# Analog_Channel_Test.net
KiCad netlist of a schematic drawn in Altium Designer
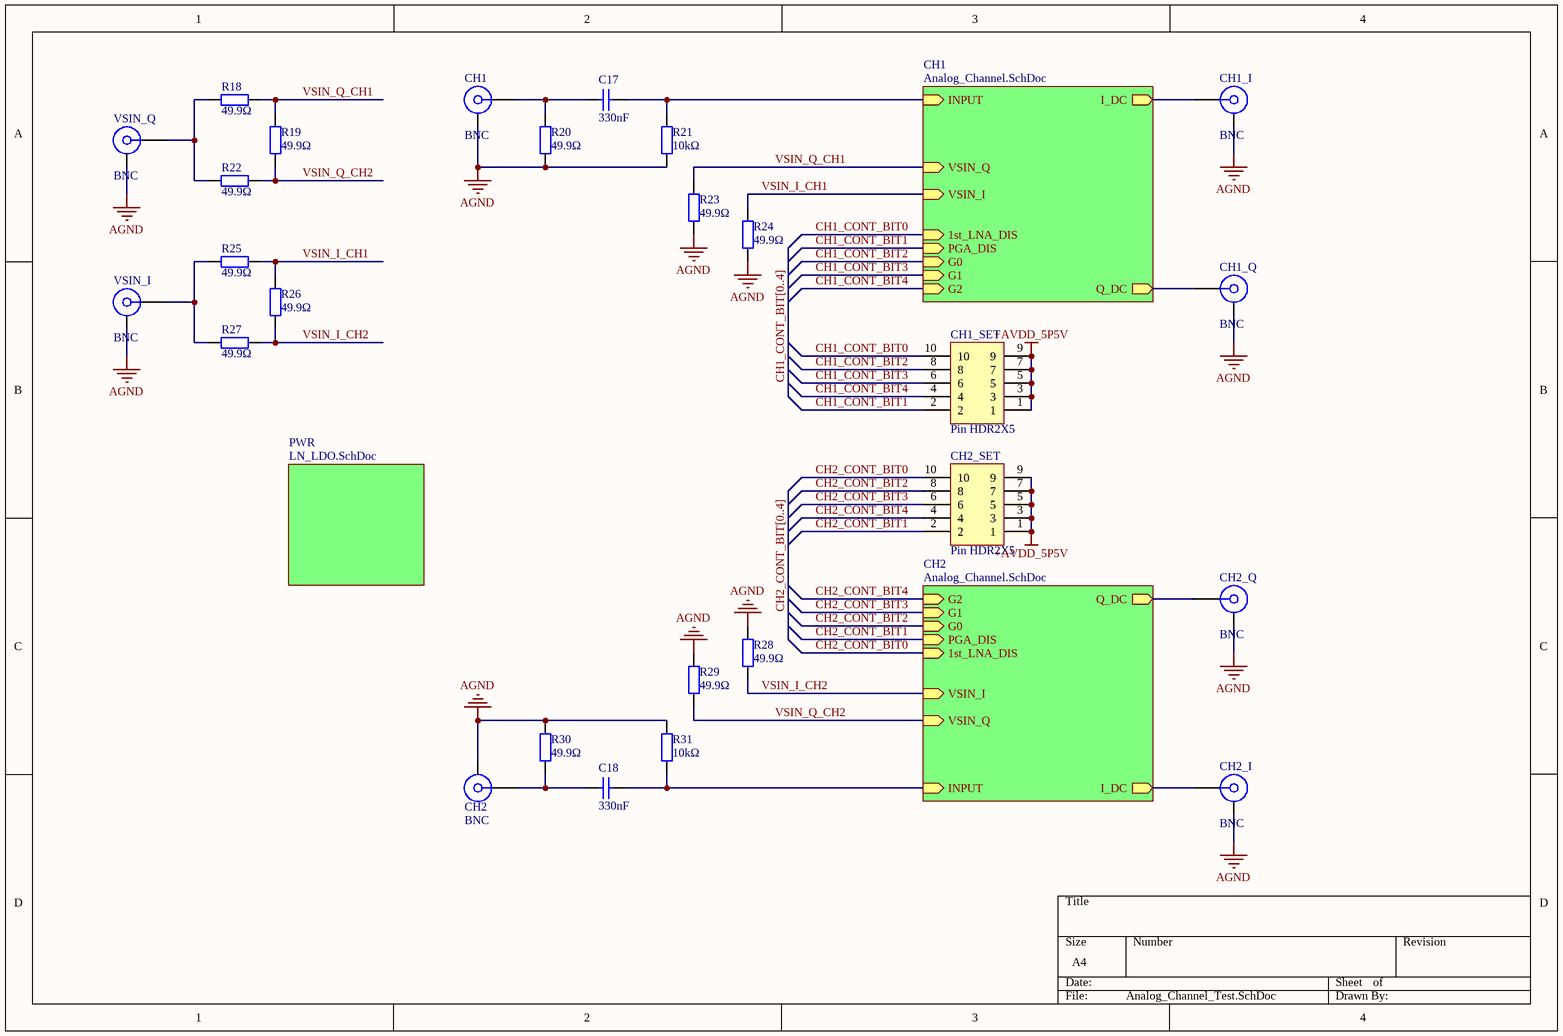
[diagram p0: Analog_Channel_Test.SchDoc]

(export (version "E")
  (design (tool "Eeschema 10.0.6"))
  (components
    (comp (ref "C17")
      (value "330nF")
      (footprint "1206_C")
      (description "贴片电容")
      (libsource (lib "Miscellaneous Devices LC") (part "1206 100nF (104) 10% 50V"))
    )
    (comp (ref "C18")
      (value "330nF")
      (footprint "1206_C")
      (description "贴片电容")
      (libsource (lib "Miscellaneous Devices LC") (part "1206 100nF (104) 10% 50V"))
    )
    (comp (ref "CH1")
      (value "BNC")
      (footprint "BNC-TYCO_1-1337542-0")
      (description "BNC-KE PIN 6.9mm distance")
      (fields (field (name "PARTNUMBER") "51K101-400A4"))
      (libsource (lib "OlvkLib") (part "BNC"))
    )
    (comp (ref "CH1_I")
      (value "BNC")
      (footprint "BNC-TYCO_1-1337542-0")
      (description "BNC-KE PIN 6.9mm distance")
      (fields (field (name "PARTNUMBER") "51K101-400A4"))
      (libsource (lib "OlvkLib") (part "BNC"))
    )
    (comp (ref "CH1_Q")
      (value "BNC")
      (footprint "BNC-TYCO_1-1337542-0")
      (description "BNC-KE PIN 6.9mm distance")
      (fields (field (name "PARTNUMBER") "51K101-400A4"))
      (libsource (lib "OlvkLib") (part "BNC"))
    )
    (comp (ref "CH1_SET")
      (value "Pin HDR2X5")
      (footprint "Pin HDR2X5/2.54mm-S")
      (libsource (lib "排针") (part "Pin HDR2X5"))
    )
    (comp (ref "CH2")
      (value "BNC")
      (footprint "BNC-TYCO_1-1337542-0")
      (description "BNC-KE PIN 6.9mm distance")
      (fields (field (name "PARTNUMBER") "51K101-400A4"))
      (libsource (lib "OlvkLib") (part "BNC"))
    )
    (comp (ref "CH2_I")
      (value "BNC")
      (footprint "BNC-TYCO_1-1337542-0")
      (description "BNC-KE PIN 6.9mm distance")
      (fields (field (name "PARTNUMBER") "51K101-400A4"))
      (libsource (lib "OlvkLib") (part "BNC"))
    )
    (comp (ref "CH2_Q")
      (value "BNC")
      (footprint "BNC-TYCO_1-1337542-0")
      (description "BNC-KE PIN 6.9mm distance")
      (fields (field (name "PARTNUMBER") "51K101-400A4"))
      (libsource (lib "OlvkLib") (part "BNC"))
    )
    (comp (ref "CH2_SET")
      (value "Pin HDR2X5")
      (footprint "Pin HDR2X5/2.54mm-S")
      (libsource (lib "排针") (part "Pin HDR2X5"))
    )
    (comp (ref "R18")
      (value "49.9Ω")
      (footprint "0603_R")
      (description "贴片电阻")
      (libsource (lib "Miscellaneous Devices LC") (part "0603 49.9Ω (49R9) 1%"))
    )
    (comp (ref "R19")
      (value "49.9Ω")
      (footprint "0603_R")
      (description "贴片电阻")
      (libsource (lib "") (part "0603 49.9Ω (49R9) 1%_2"))
    )
    (comp (ref "R20")
      (value "49.9Ω")
      (footprint "0603_R")
      (description "贴片电阻")
      (libsource (lib "") (part "0603 49.9Ω (49R9) 1%_1"))
    )
    (comp (ref "R21")
      (value "10kΩ")
      (footprint "0603_R")
      (description "贴片电阻")
      (libsource (lib "Miscellaneous Devices LC") (part "0603 10KΩ (1002) 1%"))
    )
    (comp (ref "R22")
      (value "49.9Ω")
      (footprint "0603_R")
      (description "贴片电阻")
      (libsource (lib "Miscellaneous Devices LC") (part "0603 49.9Ω (49R9) 1%"))
    )
    (comp (ref "R23")
      (value "49.9Ω")
      (footprint "0603_R")
      (description "贴片电阻")
      (libsource (lib "") (part "0603 49.9Ω (49R9) 1%_1"))
    )
    (comp (ref "R24")
      (value "49.9Ω")
      (footprint "0603_R")
      (description "贴片电阻")
      (libsource (lib "") (part "0603 49.9Ω (49R9) 1%_1"))
    )
    (comp (ref "R25")
      (value "49.9Ω")
      (footprint "0603_R")
      (description "贴片电阻")
      (libsource (lib "Miscellaneous Devices LC") (part "0603 49.9Ω (49R9) 1%"))
    )
    (comp (ref "R26")
      (value "49.9Ω")
      (footprint "0603_R")
      (description "贴片电阻")
      (libsource (lib "") (part "0603 49.9Ω (49R9) 1%_2"))
    )
    (comp (ref "R27")
      (value "49.9Ω")
      (footprint "0603_R")
      (description "贴片电阻")
      (libsource (lib "Miscellaneous Devices LC") (part "0603 49.9Ω (49R9) 1%"))
    )
    (comp (ref "R28")
      (value "49.9Ω")
      (footprint "0603_R")
      (description "贴片电阻")
      (libsource (lib "Miscellaneous Devices LC") (part "0603 49.9Ω (49R9) 1%"))
    )
    (comp (ref "R29")
      (value "49.9Ω")
      (footprint "0603_R")
      (description "贴片电阻")
      (libsource (lib "Miscellaneous Devices LC") (part "0603 49.9Ω (49R9) 1%"))
    )
    (comp (ref "R30")
      (value "49.9Ω")
      (footprint "0603_R")
      (description "贴片电阻")
      (libsource (lib "Miscellaneous Devices LC") (part "0603 49.9Ω (49R9) 1%"))
    )
    (comp (ref "R31")
      (value "10kΩ")
      (footprint "0603_R")
      (description "贴片电阻")
      (libsource (lib "") (part "0603 10KΩ (1002) 1%_1"))
    )
    (comp (ref "VSIN_I")
      (value "BNC")
      (footprint "BNC-TYCO_1-1337542-0")
      (description "BNC-KE PIN 6.9mm distance")
      (fields (field (name "PARTNUMBER") "51K101-400A4"))
      (libsource (lib "OlvkLib") (part "BNC"))
    )
    (comp (ref "VSIN_Q")
      (value "BNC")
      (footprint "BNC-TYCO_1-1337542-0")
      (description "BNC-KE PIN 6.9mm distance")
      (fields (field (name "PARTNUMBER") "51K101-400A4"))
      (libsource (lib "OlvkLib") (part "BNC"))
    )
  )
  (nets
    (net (code "1") (name "+AVDD_5P5V") (class "Default")
      (node (ref "CH1_SET") (pin "1") (pinfunction "1_1") (pintype "passive"))
      (node (ref "CH1_SET") (pin "3") (pinfunction "3_3") (pintype "passive"))
      (node (ref "CH1_SET") (pin "5") (pinfunction "5_5") (pintype "passive"))
      (node (ref "CH1_SET") (pin "7") (pinfunction "7_7") (pintype "passive"))
      (node (ref "CH1_SET") (pin "9") (pinfunction "9_9") (pintype "passive"))
      (node (ref "CH2_SET") (pin "1") (pinfunction "1_1") (pintype "passive"))
      (node (ref "CH2_SET") (pin "3") (pinfunction "3_3") (pintype "passive"))
      (node (ref "CH2_SET") (pin "5") (pinfunction "5_5") (pintype "passive"))
      (node (ref "CH2_SET") (pin "7") (pinfunction "7_7") (pintype "passive"))
      (node (ref "CH2_SET") (pin "9") (pinfunction "9_9") (pintype "passive"))
    )
    (net (code "2") (name "/CH1_CONT_BIT0") (class "Default")
      (node (ref "CH1_SET") (pin "10") (pinfunction "10_10") (pintype "passive"))
    )
    (net (code "3") (name "/CH1_CONT_BIT1") (class "Default")
      (node (ref "CH1_SET") (pin "2") (pinfunction "2_2") (pintype "passive"))
    )
    (net (code "4") (name "/CH1_CONT_BIT2") (class "Default")
      (node (ref "CH1_SET") (pin "8") (pinfunction "8_8") (pintype "passive"))
    )
    (net (code "5") (name "/CH1_CONT_BIT3") (class "Default")
      (node (ref "CH1_SET") (pin "6") (pinfunction "6_6") (pintype "passive"))
    )
    (net (code "6") (name "/CH1_CONT_BIT4") (class "Default")
      (node (ref "CH1_SET") (pin "4") (pinfunction "4_4") (pintype "passive"))
    )
    (net (code "8") (name "/CH2_CONT_BIT0") (class "Default")
      (node (ref "CH2_SET") (pin "10") (pinfunction "10_10") (pintype "passive"))
    )
    (net (code "9") (name "/CH2_CONT_BIT1") (class "Default")
      (node (ref "CH2_SET") (pin "2") (pinfunction "2_2") (pintype "passive"))
    )
    (net (code "10") (name "/CH2_CONT_BIT2") (class "Default")
      (node (ref "CH2_SET") (pin "8") (pinfunction "8_8") (pintype "passive"))
    )
    (net (code "11") (name "/CH2_CONT_BIT3") (class "Default")
      (node (ref "CH2_SET") (pin "6") (pinfunction "6_6") (pintype "passive"))
    )
    (net (code "12") (name "/CH2_CONT_BIT4") (class "Default")
      (node (ref "CH2_SET") (pin "4") (pinfunction "4_4") (pintype "passive"))
    )
    (net (code "14") (name "/INPUT") (class "Default")
      (node (ref "C17") (pin "2") (pinfunction "2_2") (pintype "passive"))
      (node (ref "R21") (pin "2") (pinfunction "2_2") (pintype "passive"))
    )
    (net (code "15") (name "/INPUT_1") (class "Default")
      (node (ref "C18") (pin "2") (pinfunction "2_2") (pintype "passive"))
      (node (ref "R31") (pin "2") (pinfunction "2_2") (pintype "passive"))
    )
    (net (code "16") (name "/I_DC") (class "Default")
      (node (ref "CH1_I") (pin "1") (pinfunction "1_1") (pintype "passive"))
    )
    (net (code "17") (name "/I_DC_1") (class "Default")
      (node (ref "CH2_I") (pin "1") (pinfunction "1_1") (pintype "passive"))
    )
    (net (code "18") (name "/Q_DC") (class "Default")
      (node (ref "CH1_Q") (pin "1") (pinfunction "1_1") (pintype "passive"))
    )
    (net (code "19") (name "/Q_DC_1") (class "Default")
      (node (ref "CH2_Q") (pin "1") (pinfunction "1_1") (pintype "passive"))
    )
    (net (code "20") (name "/VSIN_I_CH1") (class "Default")
      (node (ref "R24") (pin "2") (pinfunction "2_2") (pintype "passive"))
      (node (ref "R25") (pin "1") (pinfunction "1_1") (pintype "passive"))
      (node (ref "R26") (pin "1") (pinfunction "1_1") (pintype "passive"))
    )
    (net (code "21") (name "/VSIN_I_CH2") (class "Default")
      (node (ref "R26") (pin "2") (pinfunction "2_2") (pintype "passive"))
      (node (ref "R27") (pin "1") (pinfunction "1_1") (pintype "passive"))
      (node (ref "R28") (pin "2") (pinfunction "2_2") (pintype "passive"))
    )
    (net (code "22") (name "/VSIN_Q_CH1") (class "Default")
      (node (ref "R18") (pin "1") (pinfunction "1_1") (pintype "passive"))
      (node (ref "R19") (pin "1") (pinfunction "1_1") (pintype "passive"))
      (node (ref "R23") (pin "2") (pinfunction "2_2") (pintype "passive"))
    )
    (net (code "23") (name "/VSIN_Q_CH2") (class "Default")
      (node (ref "R19") (pin "2") (pinfunction "2_2") (pintype "passive"))
      (node (ref "R22") (pin "1") (pinfunction "1_1") (pintype "passive"))
      (node (ref "R29") (pin "2") (pinfunction "2_2") (pintype "passive"))
    )
    (net (code "24") (name "AGND") (class "Default")
      (node (ref "CH1") (pin "MH") (pinfunction "MH_MH") (pintype "passive"))
      (node (ref "CH1_I") (pin "MH") (pinfunction "MH_MH") (pintype "passive"))
      (node (ref "CH1_Q") (pin "MH") (pinfunction "MH_MH") (pintype "passive"))
      (node (ref "CH2") (pin "MH") (pinfunction "MH_MH") (pintype "passive"))
      (node (ref "CH2_I") (pin "MH") (pinfunction "MH_MH") (pintype "passive"))
      (node (ref "CH2_Q") (pin "MH") (pinfunction "MH_MH") (pintype "passive"))
      (node (ref "R20") (pin "1") (pinfunction "1_1") (pintype "passive"))
      (node (ref "R21") (pin "1") (pinfunction "1_1") (pintype "passive"))
      (node (ref "R23") (pin "1") (pinfunction "1_1") (pintype "passive"))
      (node (ref "R24") (pin "1") (pinfunction "1_1") (pintype "passive"))
      (node (ref "R28") (pin "1") (pinfunction "1_1") (pintype "passive"))
      (node (ref "R29") (pin "1") (pinfunction "1_1") (pintype "passive"))
      (node (ref "R30") (pin "1") (pinfunction "1_1") (pintype "passive"))
      (node (ref "R31") (pin "1") (pinfunction "1_1") (pintype "passive"))
      (node (ref "VSIN_I") (pin "MH") (pinfunction "MH_MH") (pintype "passive"))
      (node (ref "VSIN_Q") (pin "MH") (pinfunction "MH_MH") (pintype "passive"))
    )
    (net (code "25") (name "Net-(C17-Pad1)") (class "Default")
      (node (ref "C17") (pin "1") (pinfunction "1_1") (pintype "passive"))
      (node (ref "CH1") (pin "1") (pinfunction "1_1") (pintype "passive"))
      (node (ref "R20") (pin "2") (pinfunction "2_2") (pintype "passive"))
    )
    (net (code "26") (name "Net-(C18-Pad1)") (class "Default")
      (node (ref "C18") (pin "1") (pinfunction "1_1") (pintype "passive"))
      (node (ref "CH2") (pin "1") (pinfunction "1_1") (pintype "passive"))
      (node (ref "R30") (pin "2") (pinfunction "2_2") (pintype "passive"))
    )
    (net (code "27") (name "Net-(R18-Pad2)") (class "Default")
      (node (ref "R18") (pin "2") (pinfunction "2_2") (pintype "passive"))
      (node (ref "R22") (pin "2") (pinfunction "2_2") (pintype "passive"))
      (node (ref "VSIN_Q") (pin "1") (pinfunction "1_1") (pintype "passive"))
    )
    (net (code "28") (name "Net-(R25-Pad2)") (class "Default")
      (node (ref "R25") (pin "2") (pinfunction "2_2") (pintype "passive"))
      (node (ref "R27") (pin "2") (pinfunction "2_2") (pintype "passive"))
      (node (ref "VSIN_I") (pin "1") (pinfunction "1_1") (pintype "passive"))
    )
  )
)
